# afe_revC.net
KiCad netlist of a schematic drawn in EAGLE
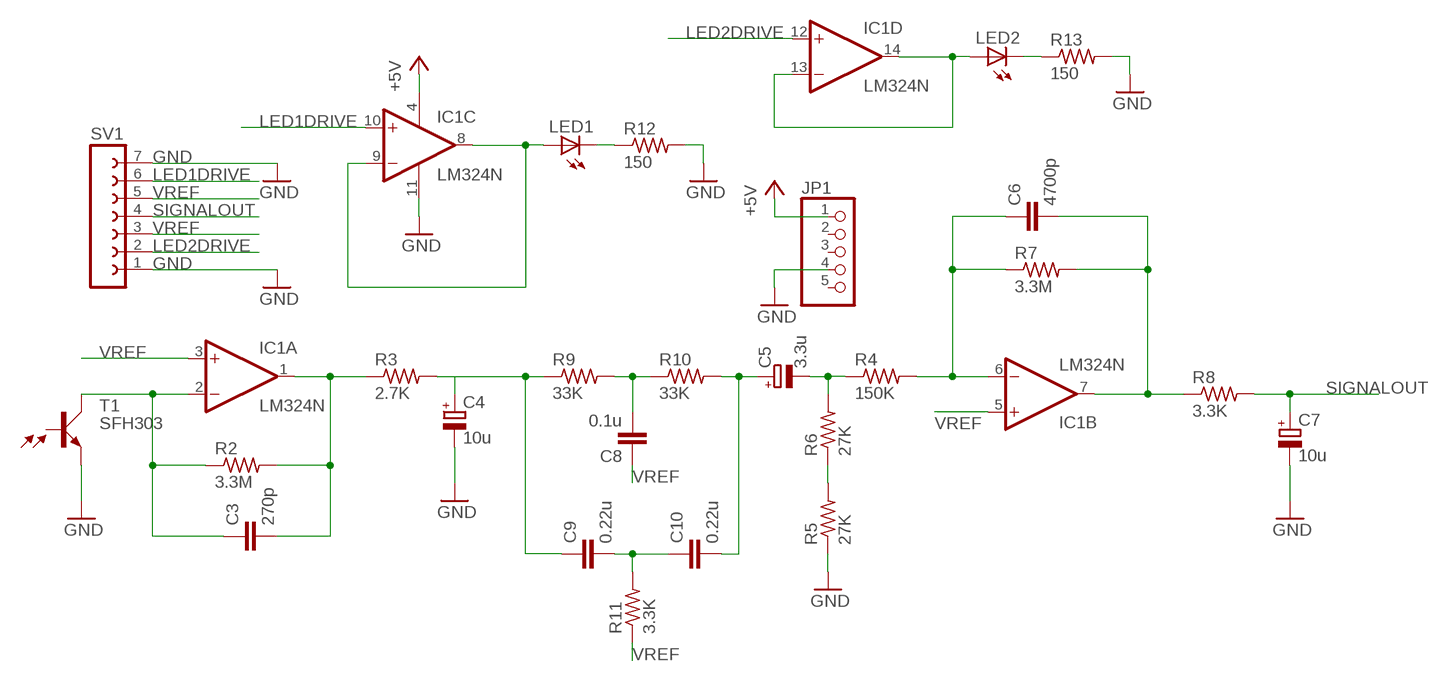
[diagram p0: schematic, sheet 1]

(export (version "E")
  (design (tool "Eeschema 10.0.6"))
  (components
    (comp (ref "C3")
      (value "270p")
      (footprint "eagle-import:C050-024X044")
      (libsource (lib "eagle-import") (part "C-EU050-024X044"))
    )
    (comp (ref "C4")
      (value "10u")
      (footprint "eagle-import:E2,5-5")
      (libsource (lib "eagle-import") (part "CPOL-EUE2.5-5"))
    )
    (comp (ref "C5")
      (value "3.3u")
      (footprint "eagle-import:E2,5-5")
      (libsource (lib "eagle-import") (part "CPOL-EUE2.5-5"))
    )
    (comp (ref "C6")
      (value "4700p")
      (footprint "eagle-import:C050-024X044")
      (libsource (lib "eagle-import") (part "C-EU050-024X044"))
    )
    (comp (ref "C7")
      (value "10u")
      (footprint "eagle-import:E2,5-5")
      (libsource (lib "eagle-import") (part "CPOL-EUE2.5-5"))
    )
    (comp (ref "C8")
      (value "0.1u")
      (footprint "eagle-import:C050-024X044")
      (libsource (lib "eagle-import") (part "C-EU050-024X044"))
    )
    (comp (ref "C9")
      (value "0.22u")
      (footprint "eagle-import:C102-043X133")
      (libsource (lib "eagle-import") (part "C-EU102-043X133"))
    )
    (comp (ref "C10")
      (value "0.22u")
      (footprint "eagle-import:C102-043X133")
      (libsource (lib "eagle-import") (part "C-EU102-043X133"))
    )
    (comp (ref "IC1")
      (value "LM324N")
      (footprint "eagle-import:DIL14")
      (libsource (lib "eagle-import") (part "LM324N"))
    )
    (comp (ref "JP1")
      (value "PINHD-1X5")
      (footprint "eagle-import:1X05")
      (libsource (lib "eagle-import") (part "PINHD-1X5"))
    )
    (comp (ref "LED1")
      (value "LED5MM")
      (footprint "eagle-import:LED5MM")
      (libsource (lib "eagle-import") (part "LED5MM"))
    )
    (comp (ref "LED2")
      (value "LED5MM")
      (footprint "eagle-import:LED5MM")
      (libsource (lib "eagle-import") (part "LED5MM"))
    )
    (comp (ref "R2")
      (value "3.3M")
      (footprint "eagle-import:0207_10")
      (libsource (lib "eagle-import") (part "R-US_0207/10"))
    )
    (comp (ref "R3")
      (value "2.7K")
      (footprint "eagle-import:0207_10")
      (libsource (lib "eagle-import") (part "R-US_0207/10"))
    )
    (comp (ref "R4")
      (value "150K")
      (footprint "eagle-import:0207_10")
      (libsource (lib "eagle-import") (part "R-US_0207/10"))
    )
    (comp (ref "R5")
      (value "27K")
      (footprint "eagle-import:0207_10")
      (libsource (lib "eagle-import") (part "R-US_0207/10"))
    )
    (comp (ref "R6")
      (value "27K")
      (footprint "eagle-import:0207_10")
      (libsource (lib "eagle-import") (part "R-US_0207/10"))
    )
    (comp (ref "R7")
      (value "3.3M")
      (footprint "eagle-import:0207_10")
      (libsource (lib "eagle-import") (part "R-US_0207/10"))
    )
    (comp (ref "R8")
      (value "3.3K")
      (footprint "eagle-import:0207_10")
      (libsource (lib "eagle-import") (part "R-US_0207/10"))
    )
    (comp (ref "R9")
      (value "33K")
      (footprint "eagle-import:0207_10")
      (libsource (lib "eagle-import") (part "R-US_0207/10"))
    )
    (comp (ref "R10")
      (value "33K")
      (footprint "eagle-import:0207_10")
      (libsource (lib "eagle-import") (part "R-US_0207/10"))
    )
    (comp (ref "R11")
      (value "3.3K")
      (footprint "eagle-import:0207_10")
      (libsource (lib "eagle-import") (part "R-US_0207/10"))
    )
    (comp (ref "R12")
      (value "150")
      (footprint "eagle-import:0207_10")
      (libsource (lib "eagle-import") (part "R-US_0207/10"))
    )
    (comp (ref "R13")
      (value "150")
      (footprint "eagle-import:0207_10")
      (libsource (lib "eagle-import") (part "R-US_0207/10"))
    )
    (comp (ref "SV1")
      (value "FE07-1")
      (footprint "eagle-import:FE07")
      (libsource (lib "eagle-import") (part "FE07-1"))
    )
    (comp (ref "T1")
      (value "SFH303")
      (footprint "eagle-import:SFH303")
      (libsource (lib "eagle-import") (part "SFH303"))
    )
  )
  (nets
    (net (code "1") (name "+5V") (class "Default")
      (node (ref "IC1") (pin "4") (pinfunction "V+_4") (pintype "power_in"))
      (node (ref "JP1") (pin "1") (pinfunction "1_1") (pintype "passive"))
    )
    (net (code "2") (name "/LED1DRIVE") (class "Default")
      (node (ref "IC1") (pin "10") (pinfunction "+IN_10") (pintype "input"))
      (node (ref "SV1") (pin "6") (pinfunction "6_6") (pintype "passive"))
    )
    (net (code "3") (name "/LED2DRIVE") (class "Default")
      (node (ref "IC1") (pin "12") (pinfunction "+IN_12") (pintype "input"))
      (node (ref "SV1") (pin "2") (pinfunction "2_2") (pintype "passive"))
    )
    (net (code "4") (name "/SIGNALOUT") (class "Default")
      (node (ref "C7") (pin "+") (pinfunction "+_+") (pintype "passive"))
      (node (ref "R8") (pin "2") (pinfunction "2_2") (pintype "passive"))
      (node (ref "SV1") (pin "4") (pinfunction "4_4") (pintype "passive"))
    )
    (net (code "5") (name "/VREF") (class "Default")
      (node (ref "C8") (pin "1") (pinfunction "1_1") (pintype "passive"))
      (node (ref "IC1") (pin "3") (pinfunction "+IN_3") (pintype "input"))
      (node (ref "IC1") (pin "5") (pinfunction "+IN_5") (pintype "input"))
      (node (ref "R11") (pin "1") (pinfunction "1_1") (pintype "passive"))
      (node (ref "SV1") (pin "3") (pinfunction "3_3") (pintype "passive"))
      (node (ref "SV1") (pin "5") (pinfunction "5_5") (pintype "passive"))
    )
    (net (code "6") (name "GND") (class "Default")
      (node (ref "C4") (pin "-") (pinfunction "-_-") (pintype "passive"))
      (node (ref "C7") (pin "-") (pinfunction "-_-") (pintype "passive"))
      (node (ref "IC1") (pin "11") (pinfunction "V-_11") (pintype "power_in"))
      (node (ref "JP1") (pin "4") (pinfunction "4_4") (pintype "passive"))
      (node (ref "R12") (pin "2") (pinfunction "2_2") (pintype "passive"))
      (node (ref "R13") (pin "2") (pinfunction "2_2") (pintype "passive"))
      (node (ref "R5") (pin "1") (pinfunction "1_1") (pintype "passive"))
      (node (ref "SV1") (pin "1") (pinfunction "1_1") (pintype "passive"))
      (node (ref "SV1") (pin "7") (pinfunction "7_7") (pintype "passive"))
      (node (ref "T1") (pin "1") (pinfunction "E_1") (pintype "passive"))
    )
    (net (code "7") (name "Net-(C4-Pad+)") (class "Default")
      (node (ref "C4") (pin "+") (pinfunction "+_+") (pintype "passive"))
      (node (ref "C9") (pin "1") (pinfunction "1_1") (pintype "passive"))
      (node (ref "R3") (pin "2") (pinfunction "2_2") (pintype "passive"))
      (node (ref "R9") (pin "1") (pinfunction "1_1") (pintype "passive"))
    )
    (net (code "8") (name "Net-(C5-Pad-)") (class "Default")
      (node (ref "C5") (pin "-") (pinfunction "-_-") (pintype "passive"))
      (node (ref "R4") (pin "1") (pinfunction "1_1") (pintype "passive"))
      (node (ref "R6") (pin "2") (pinfunction "2_2") (pintype "passive"))
    )
    (net (code "9") (name "Net-(C8-Pad2)") (class "Default")
      (node (ref "C8") (pin "2") (pinfunction "2_2") (pintype "passive"))
      (node (ref "R10") (pin "1") (pinfunction "1_1") (pintype "passive"))
      (node (ref "R9") (pin "2") (pinfunction "2_2") (pintype "passive"))
    )
    (net (code "10") (name "Net-(C10-Pad1)") (class "Default")
      (node (ref "C10") (pin "1") (pinfunction "1_1") (pintype "passive"))
      (node (ref "C9") (pin "2") (pinfunction "2_2") (pintype "passive"))
      (node (ref "R11") (pin "2") (pinfunction "2_2") (pintype "passive"))
    )
    (net (code "11") (name "Net-(C10-Pad2)") (class "Default")
      (node (ref "C10") (pin "2") (pinfunction "2_2") (pintype "passive"))
      (node (ref "C5") (pin "+") (pinfunction "+_+") (pintype "passive"))
      (node (ref "R10") (pin "2") (pinfunction "2_2") (pintype "passive"))
    )
    (net (code "12") (name "Net-(IC1A--IN)") (class "Default")
      (node (ref "C3") (pin "1") (pinfunction "1_1") (pintype "passive"))
      (node (ref "IC1") (pin "2") (pinfunction "-IN_2") (pintype "input"))
      (node (ref "R2") (pin "1") (pinfunction "1_1") (pintype "passive"))
      (node (ref "T1") (pin "2") (pinfunction "C_2") (pintype "passive"))
    )
    (net (code "13") (name "Net-(IC1A-OUT)") (class "Default")
      (node (ref "C3") (pin "2") (pinfunction "2_2") (pintype "passive"))
      (node (ref "IC1") (pin "1") (pinfunction "OUT_1") (pintype "output"))
      (node (ref "R2") (pin "2") (pinfunction "2_2") (pintype "passive"))
      (node (ref "R3") (pin "1") (pinfunction "1_1") (pintype "passive"))
    )
    (net (code "14") (name "Net-(IC1B--IN)") (class "Default")
      (node (ref "C6") (pin "1") (pinfunction "1_1") (pintype "passive"))
      (node (ref "IC1") (pin "6") (pinfunction "-IN_6") (pintype "input"))
      (node (ref "R4") (pin "2") (pinfunction "2_2") (pintype "passive"))
      (node (ref "R7") (pin "1") (pinfunction "1_1") (pintype "passive"))
    )
    (net (code "15") (name "Net-(IC1B-OUT)") (class "Default")
      (node (ref "C6") (pin "2") (pinfunction "2_2") (pintype "passive"))
      (node (ref "IC1") (pin "7") (pinfunction "OUT_7") (pintype "output"))
      (node (ref "R7") (pin "2") (pinfunction "2_2") (pintype "passive"))
      (node (ref "R8") (pin "1") (pinfunction "1_1") (pintype "passive"))
    )
    (net (code "16") (name "Net-(IC1C--IN)") (class "Default")
      (node (ref "IC1") (pin "8") (pinfunction "OUT_8") (pintype "output"))
      (node (ref "IC1") (pin "9") (pinfunction "-IN_9") (pintype "input"))
      (node (ref "LED1") (pin "A") (pinfunction "A_A") (pintype "passive"))
    )
    (net (code "17") (name "Net-(IC1D--IN)") (class "Default")
      (node (ref "IC1") (pin "13") (pinfunction "-IN_13") (pintype "input"))
      (node (ref "IC1") (pin "14") (pinfunction "OUT_14") (pintype "output"))
      (node (ref "LED2") (pin "A") (pinfunction "A_A") (pintype "passive"))
    )
    (net (code "18") (name "Net-(LED1-C)") (class "Default")
      (node (ref "LED1") (pin "K") (pinfunction "C_K") (pintype "passive"))
      (node (ref "R12") (pin "1") (pinfunction "1_1") (pintype "passive"))
    )
    (net (code "19") (name "Net-(LED2-C)") (class "Default")
      (node (ref "LED2") (pin "K") (pinfunction "C_K") (pintype "passive"))
      (node (ref "R13") (pin "1") (pinfunction "1_1") (pintype "passive"))
    )
    (net (code "20") (name "Net-(R5-Pad2)") (class "Default")
      (node (ref "R5") (pin "2") (pinfunction "2_2") (pintype "passive"))
      (node (ref "R6") (pin "1") (pinfunction "1_1") (pintype "passive"))
    )
    (net (code "21") (name "unconnected-(JP1-Pad2)") (class "Default")
      (node (ref "JP1") (pin "2") (pinfunction "2_2") (pintype "passive"))
    )
    (net (code "22") (name "unconnected-(JP1-Pad3)") (class "Default")
      (node (ref "JP1") (pin "3") (pinfunction "3_3") (pintype "passive"))
    )
    (net (code "23") (name "unconnected-(JP1-Pad5)") (class "Default")
      (node (ref "JP1") (pin "5") (pinfunction "5_5") (pintype "passive"))
    )
    (net (code "24") (name "unconnected-(T1-B-Pad3)") (class "Default")
      (node (ref "T1") (pin "3") (pinfunction "B_3") (pintype "passive"))
    )
  )
)
